# Main.net
KiCad netlist of a schematic drawn in Altium Designer
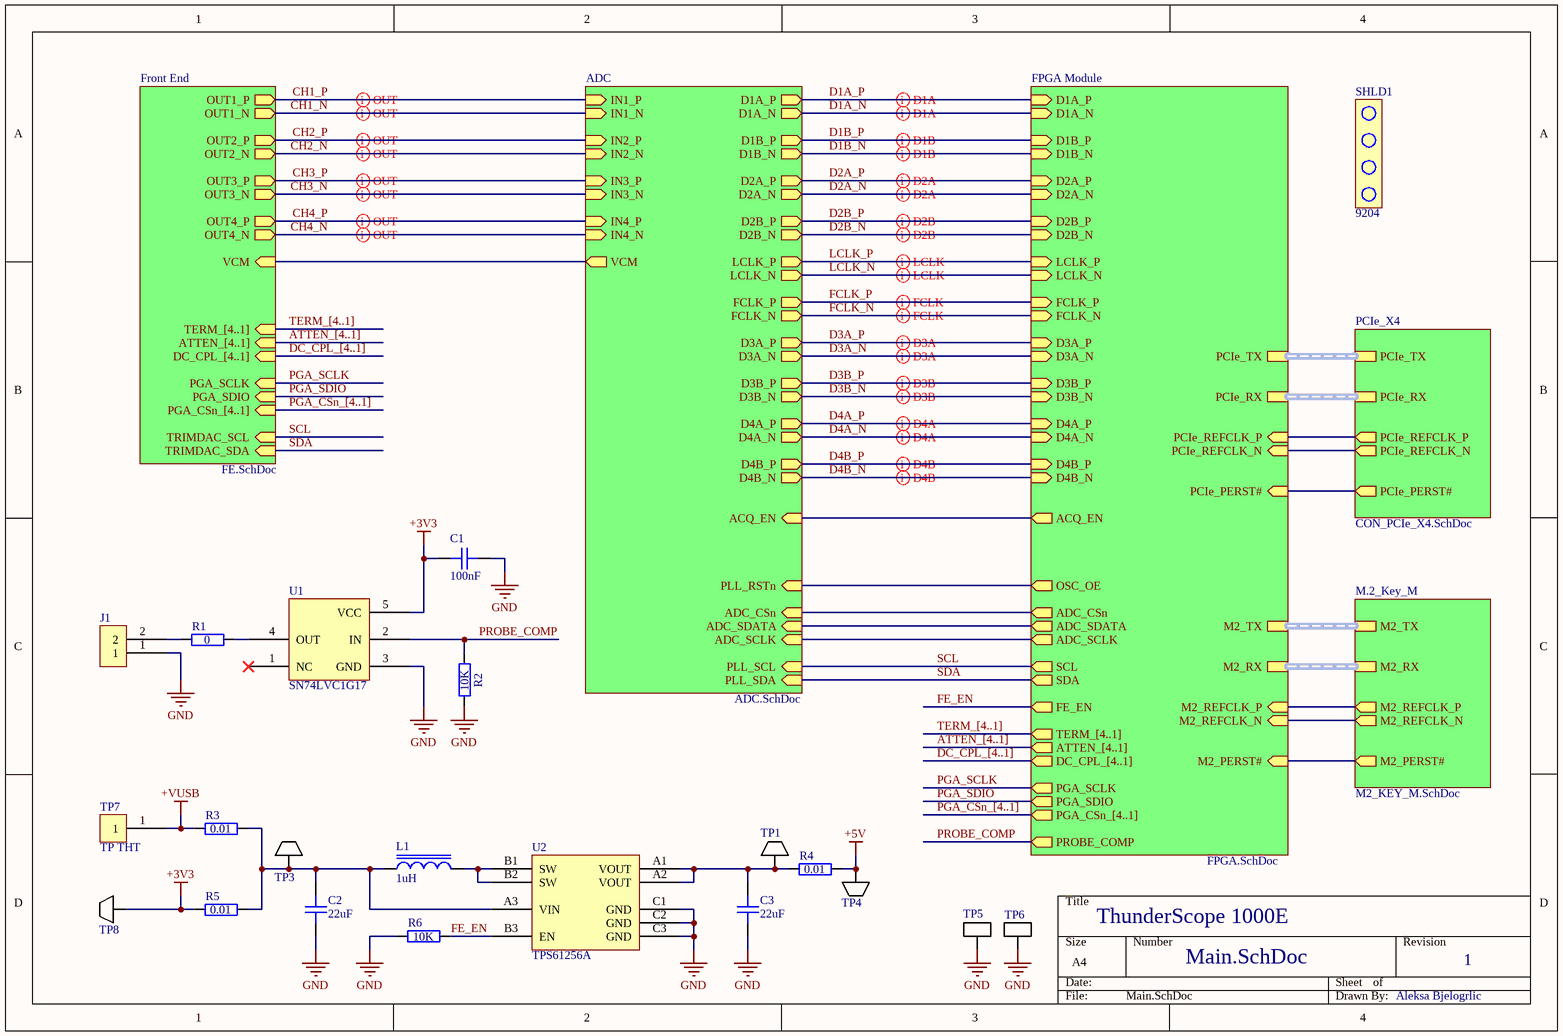
[diagram p0: Main.SchDoc]

(export (version "E")
  (design (tool "Eeschema 10.0.6"))
  (components
    (comp (ref "C1")
      (value "100nF")
      (footprint "GEN_C_0402")
      (libsource (lib "DSO") (part "CAP 100nF 16V X7R 0402"))
    )
    (comp (ref "C2")
      (value "22uF")
      (footprint "GEN_C_0805")
      (libsource (lib "DSO") (part "CAP 22uF 25V X5R 0805"))
    )
    (comp (ref "C3")
      (value "22uF")
      (footprint "GEN_C_0805")
      (libsource (lib "DSO") (part "CAP 22uF 25V X5R 0805"))
    )
    (comp (ref "J1")
      (value "TSW-101-08-F-D-RA")
      (footprint "GEN_2.54mm_1x2_Pin_TH_RA")
      (libsource (lib "DSO") (part "CONN 2.54mm 2 Pin TH RA"))
    )
    (comp (ref "L1")
      (value "1uH")
      (footprint "GEN_L_1210")
      (libsource (lib "DSO") (part "IND 1uH 3.1A 45 MOHM 1210"))
    )
    (comp (ref "R1")
      (value "0")
      (footprint "GEN_R_0402")
      (libsource (lib "DSO") (part "RES 0 OHM 1/16W 0402"))
    )
    (comp (ref "R2")
      (value "10K")
      (footprint "GEN_R_0402")
      (fields (field (name "TOLERANCE") "1%"))
      (libsource (lib "DSO") (part "RES 10K OHM 1% 1/10W 0402"))
    )
    (comp (ref "R3")
      (value "0.01")
      (footprint "GEN_R_0603")
      (fields (field (name "TOLERANCE") "1%"))
      (libsource (lib "") (part "RES 0.01 OHM 1% 1/4W 0603_1"))
    )
    (comp (ref "R4")
      (value "0.01")
      (footprint "GEN_R_0603")
      (fields (field (name "TOLERANCE") "1%"))
      (libsource (lib "DSO") (part "RES 0.01 OHM 1% 1/4W 0603"))
    )
    (comp (ref "R5")
      (value "0.01")
      (footprint "GEN_R_0603")
      (fields (field (name "TOLERANCE") "1%"))
      (libsource (lib "") (part "RES 0.01 OHM 1% 1/4W 0603_1"))
    )
    (comp (ref "R6")
      (value "10K")
      (footprint "GEN_R_0402")
      (fields (field (name "TOLERANCE") "1%"))
      (libsource (lib "") (part "RES 10K OHM 1% 1/10W 0402_1"))
    )
    (comp (ref "SHLD1") (value "9204") (libsource (lib "DSO") (part "PCIe IO Shield")))
    (comp (ref "TP1") (value "5015") (footprint "KEY_5015") (libsource (lib "DSO") (part "TP KEYSTONE 5015")))
    (comp (ref "TP3") (value "5015") (footprint "KEY_5015") (libsource (lib "DSO") (part "TP KEYSTONE 5015")))
    (comp (ref "TP4") (value "5015") (footprint "KEY_5015") (libsource (lib "DSO") (part "TP KEYSTONE 5015")))
    (comp (ref "TP5") (value "5019") (footprint "KEY_5019") (libsource (lib "DSO") (part "TP KEYSTONE 5019")))
    (comp (ref "TP6") (value "5019") (footprint "KEY_5019") (libsource (lib "DSO") (part "TP KEYSTONE 5019")))
    (comp (ref "TP7") (value "TP THT") (footprint "GEN_1_Pin_TH_TP") (libsource (lib "DSO") (part "TP THT")))
    (comp (ref "TP8") (value "5015") (footprint "KEY_5015") (libsource (lib "DSO") (part "TP KEYSTONE 5015")))
    (comp (ref "U1")
      (value "SN74LVC1G17")
      (footprint "GEN_SC-70-5")
      (libsource (lib "DSO") (part "IC BUFFER SN74LVC1G17"))
    )
    (comp (ref "U2")
      (value "TPS61256A")
      (footprint "TI_DSBGA_YFF0009")
      (libsource (lib "DSO") (part "IC BOOST TPS61256A"))
    )
  )
  (nets
    (net (code "17") (name "+3V3") (class "Default")
      (node (ref "C1") (pin "1") (pinfunction "1_1") (pintype "passive"))
      (node (ref "R5") (pin "2") (pinfunction "2_2") (pintype "passive"))
      (node (ref "TP8") (pin "1") (pinfunction "1_1") (pintype "passive"))
      (node (ref "U1") (pin "5") (pinfunction "VCC_5") (pintype "passive"))
    )
    (net (code "18") (name "+5V") (class "Default")
      (node (ref "R4") (pin "2") (pinfunction "2_2") (pintype "passive"))
      (node (ref "TP4") (pin "1") (pinfunction "1_1") (pintype "passive"))
    )
    (net (code "19") (name "+VUSB") (class "Default")
      (node (ref "R3") (pin "2") (pinfunction "2_2") (pintype "passive"))
      (node (ref "TP7") (pin "1") (pinfunction "1_1") (pintype "passive"))
    )
    (net (code "52") (name "/FE_EN") (class "Default")
      (node (ref "R6") (pin "1") (pinfunction "1_1") (pintype "passive"))
      (node (ref "U2") (pin "B3") (pinfunction "EN_B3") (pintype "passive"))
    )
    (net (code "69") (name "/PROBE_COMP") (class "Default")
      (node (ref "R2") (pin "2") (pinfunction "2_2") (pintype "passive"))
      (node (ref "U1") (pin "2") (pinfunction "IN_2") (pintype "passive"))
    )
    (net (code "74") (name "GND") (class "Default")
      (node (ref "C1") (pin "2") (pinfunction "2_2") (pintype "passive"))
      (node (ref "C2") (pin "1") (pinfunction "1_1") (pintype "passive"))
      (node (ref "C3") (pin "1") (pinfunction "1_1") (pintype "passive"))
      (node (ref "J1") (pin "1") (pinfunction "1_1") (pintype "passive"))
      (node (ref "R2") (pin "1") (pinfunction "1_1") (pintype "passive"))
      (node (ref "R6") (pin "2") (pinfunction "2_2") (pintype "passive"))
      (node (ref "TP5") (pin "1") (pinfunction "1_1") (pintype "passive"))
      (node (ref "TP6") (pin "1") (pinfunction "1_1") (pintype "passive"))
      (node (ref "U1") (pin "3") (pinfunction "GND_3") (pintype "passive"))
      (node (ref "U2") (pin "C1") (pinfunction "GND_C1") (pintype "passive"))
      (node (ref "U2") (pin "C2") (pinfunction "GND_C2") (pintype "passive"))
      (node (ref "U2") (pin "C3") (pinfunction "GND_C3") (pintype "passive"))
    )
    (net (code "75") (name "Net-(C3-Pad2)") (class "Default")
      (node (ref "C3") (pin "2") (pinfunction "2_2") (pintype "passive"))
      (node (ref "R4") (pin "1") (pinfunction "1_1") (pintype "passive"))
      (node (ref "TP1") (pin "1") (pinfunction "1_1") (pintype "passive"))
      (node (ref "U2") (pin "A1") (pinfunction "VOUT_A1") (pintype "passive"))
      (node (ref "U2") (pin "A2") (pinfunction "VOUT_A2") (pintype "passive"))
    )
    (net (code "76") (name "Net-(J1-Pad2)") (class "Default")
      (node (ref "J1") (pin "2") (pinfunction "2_2") (pintype "passive"))
      (node (ref "R1") (pin "1") (pinfunction "1_1") (pintype "passive"))
    )
    (net (code "77") (name "Net-(L1-Pad2)") (class "Default")
      (node (ref "L1") (pin "2") (pinfunction "2_2") (pintype "passive"))
      (node (ref "U2") (pin "B1") (pinfunction "SW_B1") (pintype "passive"))
      (node (ref "U2") (pin "B2") (pinfunction "SW_B2") (pintype "passive"))
    )
    (net (code "78") (name "Net-(U1-OUT)") (class "Default")
      (node (ref "R1") (pin "2") (pinfunction "2_2") (pintype "passive"))
      (node (ref "U1") (pin "4") (pinfunction "OUT_4") (pintype "passive"))
    )
    (net (code "79") (name "Net-(U2-VIN)") (class "Default")
      (node (ref "C2") (pin "2") (pinfunction "2_2") (pintype "passive"))
      (node (ref "L1") (pin "1") (pinfunction "1_1") (pintype "passive"))
      (node (ref "R3") (pin "1") (pinfunction "1_1") (pintype "passive"))
      (node (ref "R5") (pin "1") (pinfunction "1_1") (pintype "passive"))
      (node (ref "TP3") (pin "1") (pinfunction "1_1") (pintype "passive"))
      (node (ref "U2") (pin "A3") (pinfunction "VIN_A3") (pintype "passive"))
    )
    (net (code "80") (name "unconnected-(U1-NC-Pad1)") (class "Default")
      (node (ref "U1") (pin "1") (pinfunction "NC_1") (pintype "passive+no_connect"))
    )
  )
)
